# acf-adapter.net
KiCad netlist of a schematic drawn in EAGLE
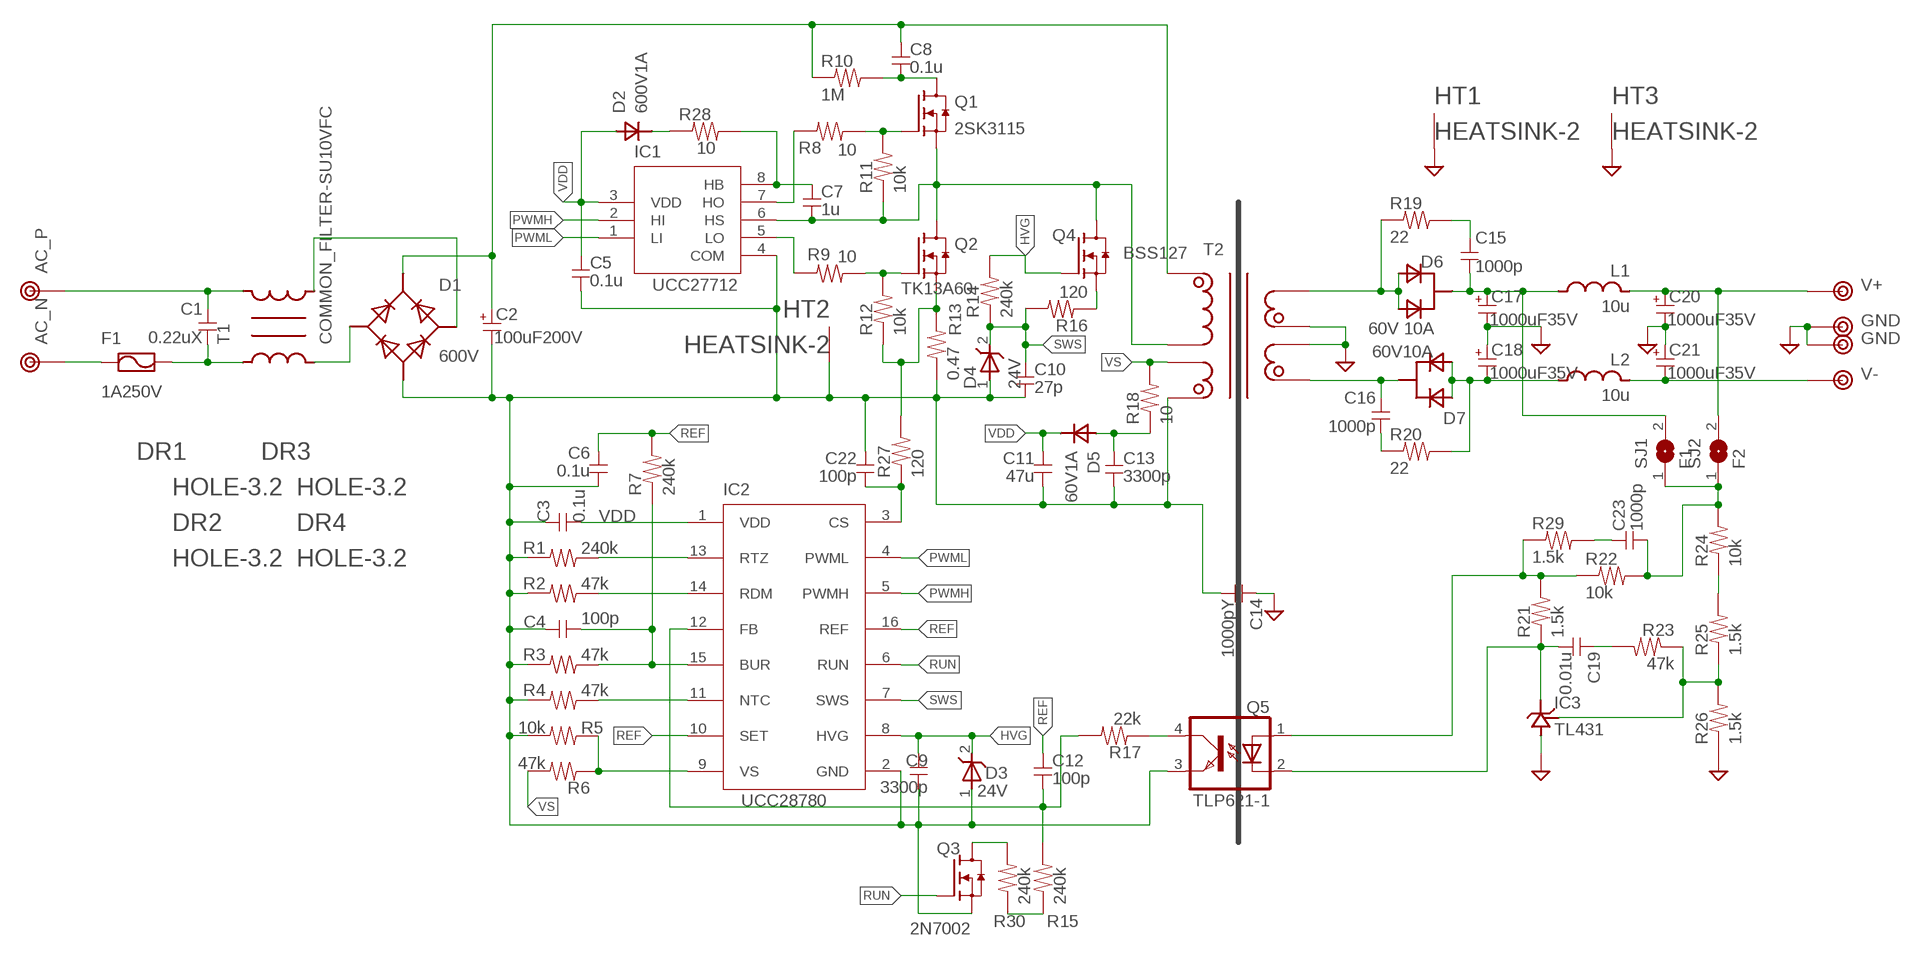
[diagram p0: schematic, sheet 1]

(export (version "E")
  (design (tool "Eeschema 10.0.6"))
  (components
    (comp (ref "C1")
      (value "0.22uX")
      (footprint "eagle-import:X-CAPACITER")
      (libsource (lib "eagle-import") (part "C-X"))
    )
    (comp (ref "C2")
      (value "100uF200V")
      (footprint "eagle-import:E5-10,5A2")
      (libsource (lib "eagle-import") (part "CPOLE5-10.5A2"))
    )
    (comp (ref "C3")
      (value "0.1u")
      (footprint "eagle-import:1608")
      (libsource (lib "eagle-import") (part "C-1608"))
    )
    (comp (ref "C4")
      (value "100p")
      (footprint "eagle-import:1608")
      (libsource (lib "eagle-import") (part "C-1608"))
    )
    (comp (ref "C5")
      (value "0.1u")
      (footprint "eagle-import:1608")
      (libsource (lib "eagle-import") (part "C-1608"))
    )
    (comp (ref "C6")
      (value "0.1u")
      (footprint "eagle-import:1608")
      (libsource (lib "eagle-import") (part "C-1608"))
    )
    (comp (ref "C7")
      (value "1u")
      (footprint "eagle-import:1608")
      (libsource (lib "eagle-import") (part "C-1608"))
    )
    (comp (ref "C8")
      (value "0.1u")
      (footprint "eagle-import:C075")
      (libsource (lib "eagle-import") (part "C-7.5"))
    )
    (comp (ref "C9")
      (value "3300p")
      (footprint "eagle-import:1608")
      (libsource (lib "eagle-import") (part "C-1608"))
    )
    (comp (ref "C10")
      (value "27p")
      (footprint "eagle-import:1608")
      (libsource (lib "eagle-import") (part "C-1608"))
    )
    (comp (ref "C11")
      (value "47u")
      (footprint "eagle-import:2012")
      (libsource (lib "eagle-import") (part "C-2012"))
    )
    (comp (ref "C12")
      (value "100p")
      (footprint "eagle-import:1608")
      (libsource (lib "eagle-import") (part "C-1608"))
    )
    (comp (ref "C13")
      (value "3300p")
      (footprint "eagle-import:1608")
      (libsource (lib "eagle-import") (part "C-1608"))
    )
    (comp (ref "C14")
      (value "1000pY")
      (footprint "eagle-import:Y-CAPACITER")
      (libsource (lib "eagle-import") (part "C-Y"))
    )
    (comp (ref "C15")
      (value "1000p")
      (footprint "eagle-import:1608")
      (libsource (lib "eagle-import") (part "C-1608"))
    )
    (comp (ref "C16")
      (value "1000p")
      (footprint "eagle-import:1608")
      (libsource (lib "eagle-import") (part "C-1608"))
    )
    (comp (ref "C17")
      (value "1000uF35V")
      (footprint "eagle-import:E5-10")
      (libsource (lib "eagle-import") (part "CPOLE5-10"))
    )
    (comp (ref "C18")
      (value "1000uF35V")
      (footprint "eagle-import:E5-10")
      (libsource (lib "eagle-import") (part "CPOLE5-10"))
    )
    (comp (ref "C19")
      (value "0.01u")
      (footprint "eagle-import:1608")
      (libsource (lib "eagle-import") (part "C-1608"))
    )
    (comp (ref "C20")
      (value "1000uF35V")
      (footprint "eagle-import:E5-10")
      (libsource (lib "eagle-import") (part "CPOLE5-10"))
    )
    (comp (ref "C21")
      (value "1000uF35V")
      (footprint "eagle-import:E5-10")
      (libsource (lib "eagle-import") (part "CPOLE5-10"))
    )
    (comp (ref "C22")
      (value "100p")
      (footprint "eagle-import:1608")
      (libsource (lib "eagle-import") (part "C-1608"))
    )
    (comp (ref "C23")
      (value "1000p")
      (footprint "eagle-import:1608")
      (libsource (lib "eagle-import") (part "C-1608"))
    )
    (comp (ref "D1")
      (value "600V")
      (footprint "eagle-import:GBU8A")
      (libsource (lib "eagle-import") (part "DIODE4-GBU8A"))
    )
    (comp (ref "D2")
      (value "600V1A")
      (footprint "eagle-import:D0204_7")
      (libsource (lib "eagle-import") (part "DIODE-7"))
    )
    (comp (ref "D3")
      (value "24V")
      (footprint "eagle-import:SOD123")
      (libsource (lib "eagle-import") (part "ZENER-SMD"))
    )
    (comp (ref "D4")
      (value "24V")
      (footprint "eagle-import:SOD123")
      (libsource (lib "eagle-import") (part "ZENER-SMD"))
    )
    (comp (ref "D5")
      (value "60V1A")
      (footprint "eagle-import:D0204_7")
      (libsource (lib "eagle-import") (part "DIODE-7"))
    )
    (comp (ref "D6")
      (value "60V 10A")
      (footprint "eagle-import:TO-220")
      (libsource (lib "eagle-import") (part "DIODE2"))
    )
    (comp (ref "D7")
      (value "60V10A")
      (footprint "eagle-import:TO-220")
      (libsource (lib "eagle-import") (part "DIODE2"))
    )
    (comp (ref "DR1")
      (value "HOLE-3.2")
      (footprint "eagle-import:HOLE_3.2")
      (libsource (lib "eagle-import") (part "HOLE-3.2"))
    )
    (comp (ref "DR2")
      (value "HOLE-3.2")
      (footprint "eagle-import:HOLE_3.2")
      (libsource (lib "eagle-import") (part "HOLE-3.2"))
    )
    (comp (ref "DR3")
      (value "HOLE-3.2")
      (footprint "eagle-import:HOLE_3.2")
      (libsource (lib "eagle-import") (part "HOLE-3.2"))
    )
    (comp (ref "DR4")
      (value "HOLE-3.2")
      (footprint "eagle-import:HOLE_3.2")
      (libsource (lib "eagle-import") (part "HOLE-3.2"))
    )
    (comp (ref "F1")
      (value "1A250V")
      (footprint "eagle-import:FUSE-5")
      (libsource (lib "eagle-import") (part "FUSE-5"))
    )
    (comp (ref "HT1")
      (value "HEATSINK-2")
      (footprint "eagle-import:HEATSINK2")
      (libsource (lib "eagle-import") (part "HEATSINK-2"))
    )
    (comp (ref "HT2")
      (value "HEATSINK-2")
      (footprint "eagle-import:HEATSINK2")
      (libsource (lib "eagle-import") (part "HEATSINK-2"))
    )
    (comp (ref "HT3")
      (value "HEATSINK-2")
      (footprint "eagle-import:HEATSINK2")
      (libsource (lib "eagle-import") (part "HEATSINK-2"))
    )
    (comp (ref "IC1")
      (value "UCC27712")
      (footprint "eagle-import:SOP8")
      (libsource (lib "eagle-import") (part "UCC27712"))
    )
    (comp (ref "IC2")
      (value "UCC28780")
      (footprint "eagle-import:SO16")
      (libsource (lib "eagle-import") (part "UCC28780"))
    )
    (comp (ref "IC3")
      (value "TL431")
      (footprint "eagle-import:TO-92")
      (libsource (lib "eagle-import") (part "TL431"))
    )
    (comp (ref "L1")
      (value "10u")
      (footprint "eagle-import:L5-7,5")
      (libsource (lib "eagle-import") (part "L-5"))
    )
    (comp (ref "L2")
      (value "10u")
      (footprint "eagle-import:L5-7,5")
      (libsource (lib "eagle-import") (part "L-5"))
    )
    (comp (ref "Q1")
      (value "2SK3115")
      (footprint "eagle-import:TO-220")
      (libsource (lib "eagle-import") (part "NMOS"))
    )
    (comp (ref "Q2")
      (value "TK13A60")
      (footprint "eagle-import:TO-220")
      (libsource (lib "eagle-import") (part "NMOS"))
    )
    (comp (ref "Q3")
      (value "2N7002")
      (footprint "eagle-import:SC59")
      (libsource (lib "eagle-import") (part "NMOS-SMD"))
    )
    (comp (ref "Q4")
      (value "BSS127")
      (footprint "eagle-import:SC59")
      (libsource (lib "eagle-import") (part "NMOS-SMD"))
    )
    (comp (ref "Q5")
      (value "TLP621-1")
      (footprint "eagle-import:DIL04")
      (libsource (lib "eagle-import") (part "TLP621-1"))
    )
    (comp (ref "R1")
      (value "240k")
      (footprint "eagle-import:1608")
      (libsource (lib "eagle-import") (part "R-1608"))
    )
    (comp (ref "R2")
      (value "47k")
      (footprint "eagle-import:1608")
      (libsource (lib "eagle-import") (part "R-1608"))
    )
    (comp (ref "R3")
      (value "47k")
      (footprint "eagle-import:1608")
      (libsource (lib "eagle-import") (part "R-1608"))
    )
    (comp (ref "R4")
      (value "47k")
      (footprint "eagle-import:1608")
      (libsource (lib "eagle-import") (part "R-1608"))
    )
    (comp (ref "R5")
      (value "10k")
      (footprint "eagle-import:1608")
      (libsource (lib "eagle-import") (part "R-1608"))
    )
    (comp (ref "R6")
      (value "47k")
      (footprint "eagle-import:1608")
      (libsource (lib "eagle-import") (part "R-1608"))
    )
    (comp (ref "R7")
      (value "240k")
      (footprint "eagle-import:1608")
      (libsource (lib "eagle-import") (part "R-1608"))
    )
    (comp (ref "R8")
      (value "10")
      (footprint "eagle-import:2012")
      (libsource (lib "eagle-import") (part "R-2012"))
    )
    (comp (ref "R9")
      (value "10")
      (footprint "eagle-import:2012")
      (libsource (lib "eagle-import") (part "R-2012"))
    )
    (comp (ref "R10")
      (value "1M")
      (footprint "eagle-import:0204_7")
      (libsource (lib "eagle-import") (part "R-7.5"))
    )
    (comp (ref "R11")
      (value "10k")
      (footprint "eagle-import:1608")
      (libsource (lib "eagle-import") (part "R-1608"))
    )
    (comp (ref "R12")
      (value "10k")
      (footprint "eagle-import:1608")
      (libsource (lib "eagle-import") (part "R-1608"))
    )
    (comp (ref "R13")
      (value "0.47")
      (footprint "eagle-import:0207_10")
      (libsource (lib "eagle-import") (part "R-10"))
    )
    (comp (ref "R14")
      (value "240k")
      (footprint "eagle-import:1608")
      (libsource (lib "eagle-import") (part "R-1608"))
    )
    (comp (ref "R15")
      (value "240k")
      (footprint "eagle-import:1608")
      (libsource (lib "eagle-import") (part "R-1608"))
    )
    (comp (ref "R16")
      (value "120")
      (footprint "eagle-import:1608")
      (libsource (lib "eagle-import") (part "R-1608"))
    )
    (comp (ref "R17")
      (value "22k")
      (footprint "eagle-import:1608")
      (libsource (lib "eagle-import") (part "R-1608"))
    )
    (comp (ref "R18")
      (value "10")
      (footprint "eagle-import:1608")
      (libsource (lib "eagle-import") (part "R-1608"))
    )
    (comp (ref "R19")
      (value "22")
      (footprint "eagle-import:0207_2V")
      (libsource (lib "eagle-import") (part "R-2.5"))
    )
    (comp (ref "R20")
      (value "22")
      (footprint "eagle-import:0207_2V")
      (libsource (lib "eagle-import") (part "R-2.5"))
    )
    (comp (ref "R21")
      (value "1.5k")
      (footprint "eagle-import:1608")
      (libsource (lib "eagle-import") (part "R-1608"))
    )
    (comp (ref "R22")
      (value "10k")
      (footprint "eagle-import:1608")
      (libsource (lib "eagle-import") (part "R-1608"))
    )
    (comp (ref "R23")
      (value "47k")
      (footprint "eagle-import:1608")
      (libsource (lib "eagle-import") (part "R-1608"))
    )
    (comp (ref "R24")
      (value "10k")
      (footprint "eagle-import:1608")
      (libsource (lib "eagle-import") (part "R-1608"))
    )
    (comp (ref "R25")
      (value "1.5k")
      (footprint "eagle-import:1608")
      (libsource (lib "eagle-import") (part "R-1608"))
    )
    (comp (ref "R26")
      (value "1.5k")
      (footprint "eagle-import:1608")
      (libsource (lib "eagle-import") (part "R-1608"))
    )
    (comp (ref "R27")
      (value "120")
      (footprint "eagle-import:1608")
      (libsource (lib "eagle-import") (part "R-1608"))
    )
    (comp (ref "R28")
      (value "10")
      (footprint "eagle-import:1608")
      (libsource (lib "eagle-import") (part "R-1608"))
    )
    (comp (ref "R29")
      (value "1.5k")
      (footprint "eagle-import:1608")
      (libsource (lib "eagle-import") (part "R-1608"))
    )
    (comp (ref "R30")
      (value "240k")
      (footprint "eagle-import:1608")
      (libsource (lib "eagle-import") (part "R-1608"))
    )
    (comp (ref "SJ1")
      (value "F1")
      (footprint "eagle-import:SJ1608")
      (libsource (lib "eagle-import") (part "SJ1608"))
    )
    (comp (ref "SJ2")
      (value "F2")
      (footprint "eagle-import:SJ1608")
      (libsource (lib "eagle-import") (part "SJ1608"))
    )
    (comp (ref "T1")
      (value "COMMON_FILTER-SU10VFC")
      (footprint "eagle-import:SU10VFC")
      (libsource (lib "eagle-import") (part "COMMON_FILTER-SU10VFC"))
    )
    (comp (ref "T2")
      (value "TRANSFORMAER_FLYBACK-PQ2620-ACF")
      (footprint "eagle-import:BPQ26_20-1112CPFR")
      (libsource (lib "eagle-import") (part "TRANSFORMAER_FLYBACK-PQ2620-ACF"))
    )
    (comp (ref "TP1")
      (value "AC_P")
      (footprint "eagle-import:TESTPIN-BIG")
      (libsource (lib "eagle-import") (part "TESTPIN-BIG"))
    )
    (comp (ref "TP2")
      (value "AC_N")
      (footprint "eagle-import:TESTPIN-BIG")
      (libsource (lib "eagle-import") (part "TESTPIN-BIG"))
    )
    (comp (ref "TP3")
      (value "V+")
      (footprint "eagle-import:TESTPIN-BIG")
      (libsource (lib "eagle-import") (part "TESTPIN-BIG"))
    )
    (comp (ref "TP4")
      (value "GND")
      (footprint "eagle-import:TESTPIN-BIG")
      (libsource (lib "eagle-import") (part "TESTPIN-BIG"))
    )
    (comp (ref "TP5")
      (value "V-")
      (footprint "eagle-import:TESTPIN-BIG")
      (libsource (lib "eagle-import") (part "TESTPIN-BIG"))
    )
    (comp (ref "TP6")
      (value "GND")
      (footprint "eagle-import:TESTPIN-BIG")
      (libsource (lib "eagle-import") (part "TESTPIN-BIG"))
    )
  )
  (nets
    (net (code "1") (name "GND") (class "Default")
      (node (ref "C14") (pin "1") (pinfunction "1_1") (pintype "passive"))
      (node (ref "C17") (pin "-") (pinfunction "2_-") (pintype "passive"))
      (node (ref "C18") (pin "+") (pinfunction "1_+") (pintype "passive"))
      (node (ref "C20") (pin "-") (pinfunction "2_-") (pintype "passive"))
      (node (ref "C21") (pin "+") (pinfunction "1_+") (pintype "passive"))
      (node (ref "HT1") (pin "HT1") (pinfunction "HT_HT1") (pintype "passive"))
      (node (ref "HT3") (pin "HT1") (pinfunction "HT_HT1") (pintype "passive"))
      (node (ref "IC3") (pin "2") (pinfunction "GND_2") (pintype "bidirectional"))
      (node (ref "R26") (pin "1") (pinfunction "1_1") (pintype "passive"))
      (node (ref "T2") (pin "10") (pinfunction "L4_N_10") (pintype "passive"))
      (node (ref "T2") (pin "9") (pinfunction "L3_P_9") (pintype "passive"))
      (node (ref "TP4") (pin "1") (pinfunction "1_1") (pintype "passive"))
      (node (ref "TP6") (pin "1") (pinfunction "1_1") (pintype "passive"))
    )
    (net (code "2") (name "HVG") (class "Default")
      (node (ref "C9") (pin "1") (pinfunction "1_1") (pintype "passive"))
      (node (ref "D3") (pin "2") (pinfunction "C_2") (pintype "bidirectional"))
      (node (ref "IC2") (pin "8") (pinfunction "HVG_8") (pintype "open_collector"))
      (node (ref "Q4") (pin "1") (pinfunction "G_1") (pintype "passive"))
      (node (ref "R14") (pin "2") (pinfunction "2_2") (pintype "passive"))
    )
    (net (code "3") (name "Net-(C1-Pad1)") (class "Default")
      (node (ref "C1") (pin "1") (pinfunction "1_1") (pintype "passive"))
      (node (ref "T1") (pin "4") (pinfunction "4_4") (pintype "passive"))
      (node (ref "TP1") (pin "1") (pinfunction "1_1") (pintype "passive"))
    )
    (net (code "4") (name "Net-(C2-1)") (class "Default")
      (node (ref "C2") (pin "+") (pinfunction "1_+") (pintype "passive"))
      (node (ref "C8") (pin "1") (pinfunction "1_1") (pintype "passive"))
      (node (ref "D1") (pin "1") (pinfunction "V+_1") (pintype "passive"))
      (node (ref "R10") (pin "1") (pinfunction "1_1") (pintype "passive"))
      (node (ref "T2") (pin "3") (pinfunction "L1_P_3") (pintype "passive"))
    )
    (net (code "5") (name "Net-(C2-2)") (class "Default")
      (node (ref "C10") (pin "2") (pinfunction "2_2") (pintype "passive"))
      (node (ref "C11") (pin "2") (pinfunction "2_2") (pintype "passive"))
      (node (ref "C13") (pin "2") (pinfunction "2_2") (pintype "passive"))
      (node (ref "C14") (pin "2") (pinfunction "2_2") (pintype "passive"))
      (node (ref "C2") (pin "-") (pinfunction "2_-") (pintype "passive"))
      (node (ref "C22") (pin "1") (pinfunction "1_1") (pintype "passive"))
      (node (ref "C3") (pin "1") (pinfunction "1_1") (pintype "passive"))
      (node (ref "C4") (pin "1") (pinfunction "1_1") (pintype "passive"))
      (node (ref "C5") (pin "2") (pinfunction "2_2") (pintype "passive"))
      (node (ref "C6") (pin "1") (pinfunction "1_1") (pintype "passive"))
      (node (ref "C9") (pin "2") (pinfunction "2_2") (pintype "passive"))
      (node (ref "D1") (pin "4") (pinfunction "V-_4") (pintype "passive"))
      (node (ref "D3") (pin "1") (pinfunction "A_1") (pintype "bidirectional"))
      (node (ref "D4") (pin "1") (pinfunction "A_1") (pintype "bidirectional"))
      (node (ref "HT2") (pin "HT1") (pinfunction "HT_HT1") (pintype "passive"))
      (node (ref "IC1") (pin "4") (pinfunction "COM_4") (pintype "power_in"))
      (node (ref "IC2") (pin "2") (pinfunction "GND_2") (pintype "power_in"))
      (node (ref "Q3") (pin "2") (pinfunction "S_2") (pintype "passive"))
      (node (ref "Q5") (pin "3") (pinfunction "EMIT_3") (pintype "passive"))
      (node (ref "R1") (pin "2") (pinfunction "2_2") (pintype "passive"))
      (node (ref "R13") (pin "1") (pinfunction "1_1") (pintype "passive"))
      (node (ref "R2") (pin "2") (pinfunction "2_2") (pintype "passive"))
      (node (ref "R3") (pin "1") (pinfunction "1_1") (pintype "passive"))
      (node (ref "R4") (pin "2") (pinfunction "2_2") (pintype "passive"))
      (node (ref "R5") (pin "2") (pinfunction "2_2") (pintype "passive"))
      (node (ref "T2") (pin "5") (pinfunction "L2_P_5") (pintype "passive"))
    )
    (net (code "6") (name "Net-(C15-Pad1)") (class "Default")
      (node (ref "C15") (pin "1") (pinfunction "1_1") (pintype "passive"))
      (node (ref "R19") (pin "2") (pinfunction "2_2") (pintype "passive"))
    )
    (net (code "7") (name "Net-(C16-Pad2)") (class "Default")
      (node (ref "C16") (pin "2") (pinfunction "2_2") (pintype "passive"))
      (node (ref "R20") (pin "1") (pinfunction "1_1") (pintype "passive"))
    )
    (net (code "8") (name "Net-(C17-1)") (class "Default")
      (node (ref "C15") (pin "2") (pinfunction "2_2") (pintype "passive"))
      (node (ref "C17") (pin "+") (pinfunction "1_+") (pintype "passive"))
      (node (ref "D6") (pin "2") (pinfunction "K_2") (pintype "passive"))
      (node (ref "L1") (pin "2") (pinfunction "1_2") (pintype "passive"))
      (node (ref "SJ1") (pin "2") (pinfunction "2_2") (pintype "passive"))
    )
    (net (code "9") (name "Net-(C18-2)") (class "Default")
      (node (ref "C18") (pin "-") (pinfunction "2_-") (pintype "passive"))
      (node (ref "D7") (pin "1") (pinfunction "A1_1") (pintype "passive"))
      (node (ref "D7") (pin "3") (pinfunction "A2_3") (pintype "passive"))
      (node (ref "L2") (pin "2") (pinfunction "1_2") (pintype "passive"))
      (node (ref "R20") (pin "2") (pinfunction "2_2") (pintype "passive"))
    )
    (net (code "10") (name "Net-(C19-Pad1)") (class "Default")
      (node (ref "C19") (pin "1") (pinfunction "1_1") (pintype "passive"))
      (node (ref "R23") (pin "2") (pinfunction "2_2") (pintype "passive"))
    )
    (net (code "11") (name "Net-(C20-1)") (class "Default")
      (node (ref "C20") (pin "+") (pinfunction "1_+") (pintype "passive"))
      (node (ref "L1") (pin "1") (pinfunction "2_1") (pintype "passive"))
      (node (ref "SJ2") (pin "2") (pinfunction "2_2") (pintype "passive"))
      (node (ref "TP3") (pin "1") (pinfunction "1_1") (pintype "passive"))
    )
    (net (code "12") (name "Net-(C21-2)") (class "Default")
      (node (ref "C21") (pin "-") (pinfunction "2_-") (pintype "passive"))
      (node (ref "L2") (pin "1") (pinfunction "2_1") (pintype "passive"))
      (node (ref "TP5") (pin "1") (pinfunction "1_1") (pintype "passive"))
    )
    (net (code "13") (name "Net-(C23-Pad1)") (class "Default")
      (node (ref "C23") (pin "1") (pinfunction "1_1") (pintype "passive"))
      (node (ref "R29") (pin "2") (pinfunction "2_2") (pintype "passive"))
    )
    (net (code "14") (name "Net-(C23-Pad2)") (class "Default")
      (node (ref "C23") (pin "2") (pinfunction "2_2") (pintype "passive"))
      (node (ref "R22") (pin "2") (pinfunction "2_2") (pintype "passive"))
      (node (ref "R24") (pin "2") (pinfunction "2_2") (pintype "passive"))
      (node (ref "SJ1") (pin "1") (pinfunction "1_1") (pintype "passive"))
      (node (ref "SJ2") (pin "1") (pinfunction "1_1") (pintype "passive"))
    )
    (net (code "15") (name "Net-(D1-AC1)") (class "Default")
      (node (ref "D1") (pin "2") (pinfunction "AC1_2") (pintype "passive"))
      (node (ref "T1") (pin "2") (pinfunction "2_2") (pintype "passive"))
    )
    (net (code "16") (name "Net-(D1-AC2)") (class "Default")
      (node (ref "D1") (pin "3") (pinfunction "AC2_3") (pintype "passive"))
      (node (ref "T1") (pin "3") (pinfunction "3_3") (pintype "passive"))
    )
    (net (code "17") (name "Net-(D2-K)") (class "Default")
      (node (ref "D2") (pin "2") (pinfunction "K_2") (pintype "passive"))
      (node (ref "R28") (pin "1") (pinfunction "1_1") (pintype "passive"))
    )
    (net (code "18") (name "Net-(D5-A)") (class "Default")
      (node (ref "C13") (pin "1") (pinfunction "1_1") (pintype "passive"))
      (node (ref "D5") (pin "1") (pinfunction "A_1") (pintype "passive"))
      (node (ref "R18") (pin "1") (pinfunction "1_1") (pintype "passive"))
    )
    (net (code "19") (name "Net-(D6-A1)") (class "Default")
      (node (ref "D6") (pin "1") (pinfunction "A1_1") (pintype "passive"))
      (node (ref "D6") (pin "3") (pinfunction "A2_3") (pintype "passive"))
      (node (ref "R19") (pin "1") (pinfunction "1_1") (pintype "passive"))
      (node (ref "T2") (pin "7") (pinfunction "L3_N_7") (pintype "passive"))
      (node (ref "T2") (pin "8") (pinfunction "L3_N_8") (pintype "passive"))
    )
    (net (code "20") (name "Net-(D7-K)") (class "Default")
      (node (ref "C16") (pin "1") (pinfunction "1_1") (pintype "passive"))
      (node (ref "D7") (pin "2") (pinfunction "K_2") (pintype "passive"))
      (node (ref "T2") (pin "11") (pinfunction "L4_P_11") (pintype "passive"))
      (node (ref "T2") (pin "12") (pinfunction "L4_P_12") (pintype "passive"))
    )
    (net (code "21") (name "Net-(F1-P$1)") (class "Default")
      (node (ref "F1") (pin "1") (pinfunction "P$1_1") (pintype "passive"))
      (node (ref "TP2") (pin "1") (pinfunction "1_1") (pintype "passive"))
    )
    (net (code "22") (name "Net-(F1-P$2)") (class "Default")
      (node (ref "C1") (pin "2") (pinfunction "2_2") (pintype "passive"))
      (node (ref "F1") (pin "2") (pinfunction "P$2_2") (pintype "passive"))
      (node (ref "T1") (pin "1") (pinfunction "1_1") (pintype "passive"))
    )
    (net (code "23") (name "Net-(IC1-HB)") (class "Default")
      (node (ref "C7") (pin "1") (pinfunction "1_1") (pintype "passive"))
      (node (ref "IC1") (pin "8") (pinfunction "HB_8") (pintype "power_in"))
      (node (ref "R28") (pin "2") (pinfunction "2_2") (pintype "passive"))
    )
    (net (code "24") (name "Net-(IC1-HO)") (class "Default")
      (node (ref "IC1") (pin "7") (pinfunction "HO_7") (pintype "output"))
      (node (ref "R8") (pin "2") (pinfunction "2_2") (pintype "passive"))
    )
    (net (code "25") (name "Net-(IC1-HS)") (class "Default")
      (node (ref "C7") (pin "2") (pinfunction "2_2") (pintype "passive"))
      (node (ref "IC1") (pin "6") (pinfunction "HS_6") (pintype "power_in"))
      (node (ref "Q1") (pin "3") (pinfunction "S_3") (pintype "passive"))
      (node (ref "Q2") (pin "2") (pinfunction "D_2") (pintype "passive"))
      (node (ref "Q4") (pin "3") (pinfunction "D_3") (pintype "passive"))
      (node (ref "R11") (pin "1") (pinfunction "1_1") (pintype "passive"))
      (node (ref "T2") (pin "1") (pinfunction "L1_N_1") (pintype "passive"))
    )
    (net (code "26") (name "Net-(IC1-LO)") (class "Default")
      (node (ref "IC1") (pin "5") (pinfunction "LO_5") (pintype "output"))
      (node (ref "R9") (pin "2") (pinfunction "2_2") (pintype "passive"))
    )
    (net (code "27") (name "Net-(IC2-BUR)") (class "Default")
      (node (ref "C4") (pin "2") (pinfunction "2_2") (pintype "passive"))
      (node (ref "IC2") (pin "15") (pinfunction "BUR_15") (pintype "input"))
      (node (ref "R3") (pin "2") (pinfunction "2_2") (pintype "passive"))
      (node (ref "R7") (pin "1") (pinfunction "1_1") (pintype "passive"))
    )
    (net (code "28") (name "Net-(IC2-CS)") (class "Default")
      (node (ref "C22") (pin "2") (pinfunction "2_2") (pintype "passive"))
      (node (ref "IC2") (pin "3") (pinfunction "CS_3") (pintype "input"))
      (node (ref "R27") (pin "1") (pinfunction "1_1") (pintype "passive"))
    )
    (net (code "29") (name "Net-(IC2-FB)") (class "Default")
      (node (ref "C12") (pin "2") (pinfunction "2_2") (pintype "passive"))
      (node (ref "IC2") (pin "12") (pinfunction "FB_12") (pintype "input"))
      (node (ref "R15") (pin "2") (pinfunction "2_2") (pintype "passive"))
      (node (ref "R17") (pin "2") (pinfunction "2_2") (pintype "passive"))
    )
    (net (code "30") (name "Net-(IC2-NTC)") (class "Default")
      (node (ref "IC2") (pin "11") (pinfunction "NTC_11") (pintype "passive"))
      (node (ref "R4") (pin "1") (pinfunction "1_1") (pintype "passive"))
    )
    (net (code "31") (name "Net-(IC2-RDM)") (class "Default")
      (node (ref "IC2") (pin "14") (pinfunction "RDM_14") (pintype "input"))
      (node (ref "R2") (pin "1") (pinfunction "1_1") (pintype "passive"))
    )
    (net (code "32") (name "Net-(IC2-RTZ)") (class "Default")
      (node (ref "IC2") (pin "13") (pinfunction "RTZ_13") (pintype "input"))
      (node (ref "R1") (pin "1") (pinfunction "1_1") (pintype "passive"))
    )
    (net (code "33") (name "Net-(IC2-VS)") (class "Default")
      (node (ref "IC2") (pin "9") (pinfunction "VS_9") (pintype "input"))
      (node (ref "R5") (pin "1") (pinfunction "1_1") (pintype "passive"))
      (node (ref "R6") (pin "1") (pinfunction "1_1") (pintype "passive"))
    )
    (net (code "34") (name "Net-(IC3-OUT)") (class "Default")
      (node (ref "C19") (pin "2") (pinfunction "2_2") (pintype "passive"))
      (node (ref "IC3") (pin "3") (pinfunction "OUT_3") (pintype "bidirectional"))
      (node (ref "Q5") (pin "2") (pinfunction "C_2") (pintype "passive"))
      (node (ref "R21") (pin "1") (pinfunction "1_1") (pintype "passive"))
    )
    (net (code "35") (name "Net-(IC3-REF)") (class "Default")
      (node (ref "IC3") (pin "1") (pinfunction "REF_1") (pintype "input"))
      (node (ref "R23") (pin "1") (pinfunction "1_1") (pintype "passive"))
      (node (ref "R25") (pin "1") (pinfunction "1_1") (pintype "passive"))
      (node (ref "R26") (pin "2") (pinfunction "2_2") (pintype "passive"))
    )
    (net (code "36") (name "Net-(Q1-D)") (class "Default")
      (node (ref "C8") (pin "2") (pinfunction "2_2") (pintype "passive"))
      (node (ref "Q1") (pin "2") (pinfunction "D_2") (pintype "passive"))
      (node (ref "R10") (pin "2") (pinfunction "2_2") (pintype "passive"))
    )
    (net (code "37") (name "Net-(Q1-G)") (class "Default")
      (node (ref "Q1") (pin "1") (pinfunction "G_1") (pintype "passive"))
      (node (ref "R11") (pin "2") (pinfunction "2_2") (pintype "passive"))
      (node (ref "R8") (pin "1") (pinfunction "1_1") (pintype "passive"))
    )
    (net (code "38") (name "Net-(Q2-G)") (class "Default")
      (node (ref "Q2") (pin "1") (pinfunction "G_1") (pintype "passive"))
      (node (ref "R12") (pin "2") (pinfunction "2_2") (pintype "passive"))
      (node (ref "R9") (pin "1") (pinfunction "1_1") (pintype "passive"))
    )
    (net (code "39") (name "Net-(Q2-S)") (class "Default")
      (node (ref "Q2") (pin "3") (pinfunction "S_3") (pintype "passive"))
      (node (ref "R12") (pin "1") (pinfunction "1_1") (pintype "passive"))
      (node (ref "R13") (pin "2") (pinfunction "2_2") (pintype "passive"))
      (node (ref "R27") (pin "2") (pinfunction "2_2") (pintype "passive"))
    )
    (net (code "40") (name "Net-(Q3-D)") (class "Default")
      (node (ref "Q3") (pin "3") (pinfunction "D_3") (pintype "passive"))
      (node (ref "R30") (pin "2") (pinfunction "2_2") (pintype "passive"))
    )
    (net (code "41") (name "Net-(Q4-S)") (class "Default")
      (node (ref "Q4") (pin "2") (pinfunction "S_2") (pintype "passive"))
      (node (ref "R16") (pin "1") (pinfunction "1_1") (pintype "passive"))
    )
    (net (code "42") (name "Net-(Q5-A)") (class "Default")
      (node (ref "Q5") (pin "1") (pinfunction "A_1") (pintype "passive"))
      (node (ref "R21") (pin "2") (pinfunction "2_2") (pintype "passive"))
      (node (ref "R22") (pin "1") (pinfunction "1_1") (pintype "passive"))
      (node (ref "R29") (pin "1") (pinfunction "1_1") (pintype "passive"))
    )
    (net (code "43") (name "Net-(Q5-COL)") (class "Default")
      (node (ref "Q5") (pin "4") (pinfunction "COL_4") (pintype "passive"))
      (node (ref "R17") (pin "1") (pinfunction "1_1") (pintype "passive"))
    )
    (net (code "44") (name "Net-(R15-Pad1)") (class "Default")
      (node (ref "R15") (pin "1") (pinfunction "1_1") (pintype "passive"))
      (node (ref "R30") (pin "1") (pinfunction "1_1") (pintype "passive"))
    )
    (net (code "45") (name "Net-(R24-Pad1)") (class "Default")
      (node (ref "R24") (pin "1") (pinfunction "1_1") (pintype "passive"))
      (node (ref "R25") (pin "2") (pinfunction "2_2") (pintype "passive"))
    )
    (net (code "46") (name "PWMH") (class "Default")
      (node (ref "IC1") (pin "2") (pinfunction "HI_2") (pintype "input"))
      (node (ref "IC2") (pin "5") (pinfunction "PWMH_5") (pintype "output"))
    )
    (net (code "47") (name "PWML") (class "Default")
      (node (ref "IC1") (pin "1") (pinfunction "LI_1") (pintype "input"))
      (node (ref "IC2") (pin "4") (pinfunction "PWML_4") (pintype "output"))
    )
    (net (code "48") (name "REF") (class "Default")
      (node (ref "C12") (pin "1") (pinfunction "1_1") (pintype "passive"))
      (node (ref "C6") (pin "2") (pinfunction "2_2") (pintype "passive"))
      (node (ref "IC2") (pin "10") (pinfunction "SET_10") (pintype "input"))
      (node (ref "IC2") (pin "16") (pinfunction "REF_16") (pintype "output"))
      (node (ref "R7") (pin "2") (pinfunction "2_2") (pintype "passive"))
    )
    (net (code "49") (name "RUN") (class "Default")
      (node (ref "IC2") (pin "6") (pinfunction "RUN_6") (pintype "output"))
      (node (ref "Q3") (pin "1") (pinfunction "G_1") (pintype "passive"))
    )
    (net (code "50") (name "SWS") (class "Default")
      (node (ref "C10") (pin "1") (pinfunction "1_1") (pintype "passive"))
      (node (ref "D4") (pin "2") (pinfunction "C_2") (pintype "bidirectional"))
      (node (ref "IC2") (pin "7") (pinfunction "SWS_7") (pintype "input"))
      (node (ref "R14") (pin "1") (pinfunction "1_1") (pintype "passive"))
      (node (ref "R16") (pin "2") (pinfunction "2_2") (pintype "passive"))
    )
    (net (code "51") (name "VDD") (class "Default")
      (node (ref "C11") (pin "1") (pinfunction "1_1") (pintype "passive"))
      (node (ref "C3") (pin "2") (pinfunction "2_2") (pintype "passive"))
      (node (ref "C5") (pin "1") (pinfunction "1_1") (pintype "passive"))
      (node (ref "D2") (pin "1") (pinfunction "A_1") (pintype "passive"))
      (node (ref "D5") (pin "2") (pinfunction "K_2") (pintype "passive"))
      (node (ref "IC1") (pin "3") (pinfunction "VDD_3") (pintype "power_in"))
      (node (ref "IC2") (pin "1") (pinfunction "VDD_1") (pintype "power_in"))
    )
    (net (code "52") (name "VS") (class "Default")
      (node (ref "R18") (pin "2") (pinfunction "2_2") (pintype "passive"))
      (node (ref "R6") (pin "2") (pinfunction "2_2") (pintype "passive"))
      (node (ref "T2") (pin "6") (pinfunction "L2_N_6") (pintype "passive"))
    )
  )
)
